# W023A.net
KiCad netlist of a schematic drawn in EAGLE
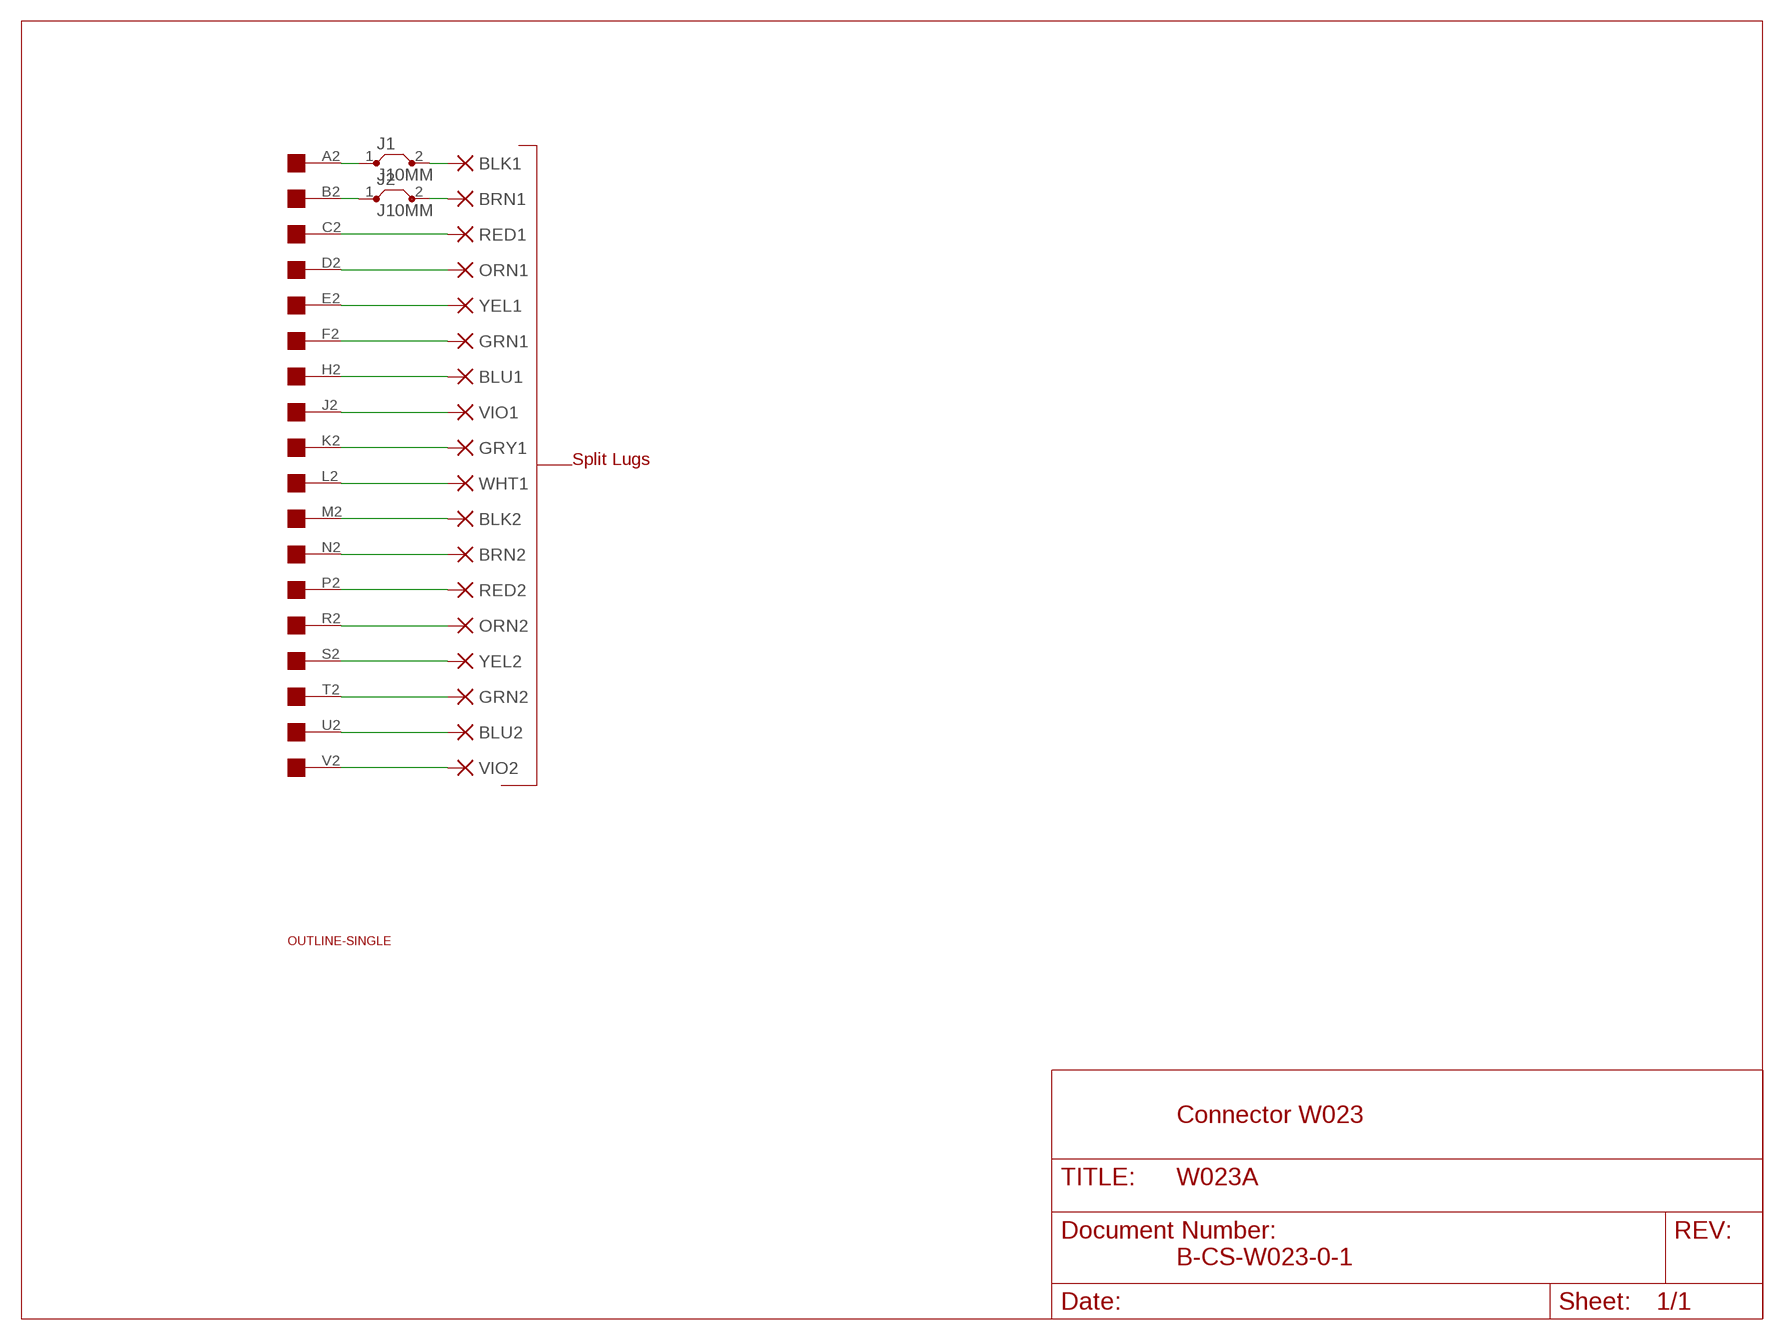
[diagram p0: schematic, sheet 1]

(export (version "E")
  (design (tool "Eeschema 10.0.6"))
  (components
    (comp (ref "BLK1")
      (value "PAD-0465")
      (footprint "eagle-import:0465")
      (libsource (lib "eagle-import") (part "PAD-0465"))
    )
    (comp (ref "BLK2")
      (value "PAD-0465")
      (footprint "eagle-import:0465")
      (libsource (lib "eagle-import") (part "PAD-0465"))
    )
    (comp (ref "BLU1")
      (value "PAD-0465")
      (footprint "eagle-import:0465")
      (libsource (lib "eagle-import") (part "PAD-0465"))
    )
    (comp (ref "BLU2")
      (value "PAD-0465")
      (footprint "eagle-import:0465")
      (libsource (lib "eagle-import") (part "PAD-0465"))
    )
    (comp (ref "BRN1")
      (value "PAD-0465")
      (footprint "eagle-import:0465")
      (libsource (lib "eagle-import") (part "PAD-0465"))
    )
    (comp (ref "BRN2")
      (value "PAD-0465")
      (footprint "eagle-import:0465")
      (libsource (lib "eagle-import") (part "PAD-0465"))
    )
    (comp (ref "GRN1")
      (value "PAD-0465")
      (footprint "eagle-import:0465")
      (libsource (lib "eagle-import") (part "PAD-0465"))
    )
    (comp (ref "GRN2")
      (value "PAD-0465")
      (footprint "eagle-import:0465")
      (libsource (lib "eagle-import") (part "PAD-0465"))
    )
    (comp (ref "GRY1")
      (value "PAD-0465")
      (footprint "eagle-import:0465")
      (libsource (lib "eagle-import") (part "PAD-0465"))
    )
    (comp (ref "J1")
      (value "J10MM")
      (footprint "eagle-import:10")
      (libsource (lib "eagle-import") (part "J10MM"))
    )
    (comp (ref "J2")
      (value "J10MM")
      (footprint "eagle-import:10")
      (libsource (lib "eagle-import") (part "J10MM"))
    )
    (comp (ref "ORN1")
      (value "PAD-0465")
      (footprint "eagle-import:0465")
      (libsource (lib "eagle-import") (part "PAD-0465"))
    )
    (comp (ref "ORN2")
      (value "PAD-0465")
      (footprint "eagle-import:0465")
      (libsource (lib "eagle-import") (part "PAD-0465"))
    )
    (comp (ref "RED1")
      (value "PAD-0465")
      (footprint "eagle-import:0465")
      (libsource (lib "eagle-import") (part "PAD-0465"))
    )
    (comp (ref "RED2")
      (value "PAD-0465")
      (footprint "eagle-import:0465")
      (libsource (lib "eagle-import") (part "PAD-0465"))
    )
    (comp (ref "U$1")
      (value "OUTLINE-SINGLE")
      (footprint "eagle-import:SINGLE")
      (libsource (lib "eagle-import") (part "OUTLINE-SINGLE"))
    )
    (comp (ref "U$2")
      (value "EDGE-1")
      (footprint "eagle-import:EDGE-CON1")
      (libsource (lib "eagle-import") (part "EDGE-1"))
    )
    (comp (ref "VIO1")
      (value "PAD-0465")
      (footprint "eagle-import:0465")
      (libsource (lib "eagle-import") (part "PAD-0465"))
    )
    (comp (ref "VIO2")
      (value "PAD-0465")
      (footprint "eagle-import:0465")
      (libsource (lib "eagle-import") (part "PAD-0465"))
    )
    (comp (ref "WHT1")
      (value "PAD-0465")
      (footprint "eagle-import:0465")
      (libsource (lib "eagle-import") (part "PAD-0465"))
    )
    (comp (ref "YEL1")
      (value "PAD-0465")
      (footprint "eagle-import:0465")
      (libsource (lib "eagle-import") (part "PAD-0465"))
    )
    (comp (ref "YEL2")
      (value "PAD-0465")
      (footprint "eagle-import:0465")
      (libsource (lib "eagle-import") (part "PAD-0465"))
    )
  )
  (nets
    (net (code "1") (name "Net-(BLK1-P)") (class "Default")
      (node (ref "BLK1") (pin "P$1") (pinfunction "P_P$1") (pintype "passive"))
      (node (ref "J1") (pin "2") (pinfunction "2_2") (pintype "passive"))
    )
    (net (code "2") (name "Net-(BLK2-P)") (class "Default")
      (node (ref "BLK2") (pin "P$1") (pinfunction "P_P$1") (pintype "passive"))
      (node (ref "U$2") (pin "M2") (pinfunction "1_M2") (pintype "bidirectional"))
    )
    (net (code "3") (name "Net-(BLU1-P)") (class "Default")
      (node (ref "BLU1") (pin "P$1") (pinfunction "P_P$1") (pintype "passive"))
      (node (ref "U$2") (pin "H2") (pinfunction "1_H2") (pintype "bidirectional"))
    )
    (net (code "4") (name "Net-(BLU2-P)") (class "Default")
      (node (ref "BLU2") (pin "P$1") (pinfunction "P_P$1") (pintype "passive"))
      (node (ref "U$2") (pin "U2") (pinfunction "1_U2") (pintype "bidirectional"))
    )
    (net (code "5") (name "Net-(BRN1-P)") (class "Default")
      (node (ref "BRN1") (pin "P$1") (pinfunction "P_P$1") (pintype "passive"))
      (node (ref "J2") (pin "2") (pinfunction "2_2") (pintype "passive"))
    )
    (net (code "6") (name "Net-(BRN2-P)") (class "Default")
      (node (ref "BRN2") (pin "P$1") (pinfunction "P_P$1") (pintype "passive"))
      (node (ref "U$2") (pin "N2") (pinfunction "1_N2") (pintype "bidirectional"))
    )
    (net (code "7") (name "Net-(GRN1-P)") (class "Default")
      (node (ref "GRN1") (pin "P$1") (pinfunction "P_P$1") (pintype "passive"))
      (node (ref "U$2") (pin "F2") (pinfunction "1_F2") (pintype "bidirectional"))
    )
    (net (code "8") (name "Net-(GRN2-P)") (class "Default")
      (node (ref "GRN2") (pin "P$1") (pinfunction "P_P$1") (pintype "passive"))
      (node (ref "U$2") (pin "T2") (pinfunction "1_T2") (pintype "bidirectional"))
    )
    (net (code "9") (name "Net-(GRY1-P)") (class "Default")
      (node (ref "GRY1") (pin "P$1") (pinfunction "P_P$1") (pintype "passive"))
      (node (ref "U$2") (pin "K2") (pinfunction "1_K2") (pintype "bidirectional"))
    )
    (net (code "10") (name "Net-(ORN1-P)") (class "Default")
      (node (ref "ORN1") (pin "P$1") (pinfunction "P_P$1") (pintype "passive"))
      (node (ref "U$2") (pin "D2") (pinfunction "1_D2") (pintype "bidirectional"))
    )
    (net (code "11") (name "Net-(ORN2-P)") (class "Default")
      (node (ref "ORN2") (pin "P$1") (pinfunction "P_P$1") (pintype "passive"))
      (node (ref "U$2") (pin "R2") (pinfunction "1_R2") (pintype "bidirectional"))
    )
    (net (code "12") (name "Net-(RED1-P)") (class "Default")
      (node (ref "RED1") (pin "P$1") (pinfunction "P_P$1") (pintype "passive"))
      (node (ref "U$2") (pin "C2") (pinfunction "1_C2") (pintype "bidirectional"))
    )
    (net (code "13") (name "Net-(RED2-P)") (class "Default")
      (node (ref "RED2") (pin "P$1") (pinfunction "P_P$1") (pintype "passive"))
      (node (ref "U$2") (pin "P2") (pinfunction "1_P2") (pintype "bidirectional"))
    )
    (net (code "14") (name "Net-(U$2A-1)") (class "Default")
      (node (ref "J1") (pin "1") (pinfunction "1_1") (pintype "passive"))
      (node (ref "U$2") (pin "A2") (pinfunction "1_A2") (pintype "bidirectional"))
    )
    (net (code "15") (name "Net-(U$2B-1)") (class "Default")
      (node (ref "J2") (pin "1") (pinfunction "1_1") (pintype "passive"))
      (node (ref "U$2") (pin "B2") (pinfunction "1_B2") (pintype "bidirectional"))
    )
    (net (code "16") (name "Net-(U$2E-1)") (class "Default")
      (node (ref "U$2") (pin "E2") (pinfunction "1_E2") (pintype "bidirectional"))
      (node (ref "YEL1") (pin "P$1") (pinfunction "P_P$1") (pintype "passive"))
    )
    (net (code "17") (name "Net-(U$2H-1)") (class "Default")
      (node (ref "U$2") (pin "J2") (pinfunction "1_J2") (pintype "bidirectional"))
      (node (ref "VIO1") (pin "P$1") (pinfunction "P_P$1") (pintype "passive"))
    )
    (net (code "18") (name "Net-(U$2J-1)") (class "Default")
      (node (ref "U$2") (pin "L2") (pinfunction "1_L2") (pintype "bidirectional"))
      (node (ref "WHT1") (pin "P$1") (pinfunction "P_P$1") (pintype "passive"))
    )
    (net (code "19") (name "Net-(U$2O-1)") (class "Default")
      (node (ref "U$2") (pin "S2") (pinfunction "1_S2") (pintype "bidirectional"))
      (node (ref "YEL2") (pin "P$1") (pinfunction "P_P$1") (pintype "passive"))
    )
    (net (code "20") (name "Net-(U$2R-1)") (class "Default")
      (node (ref "U$2") (pin "V2") (pinfunction "1_V2") (pintype "bidirectional"))
      (node (ref "VIO2") (pin "P$1") (pinfunction "P_P$1") (pintype "passive"))
    )
  )
)
